# mcu.net
KiCad netlist of a schematic drawn in Altium Designer
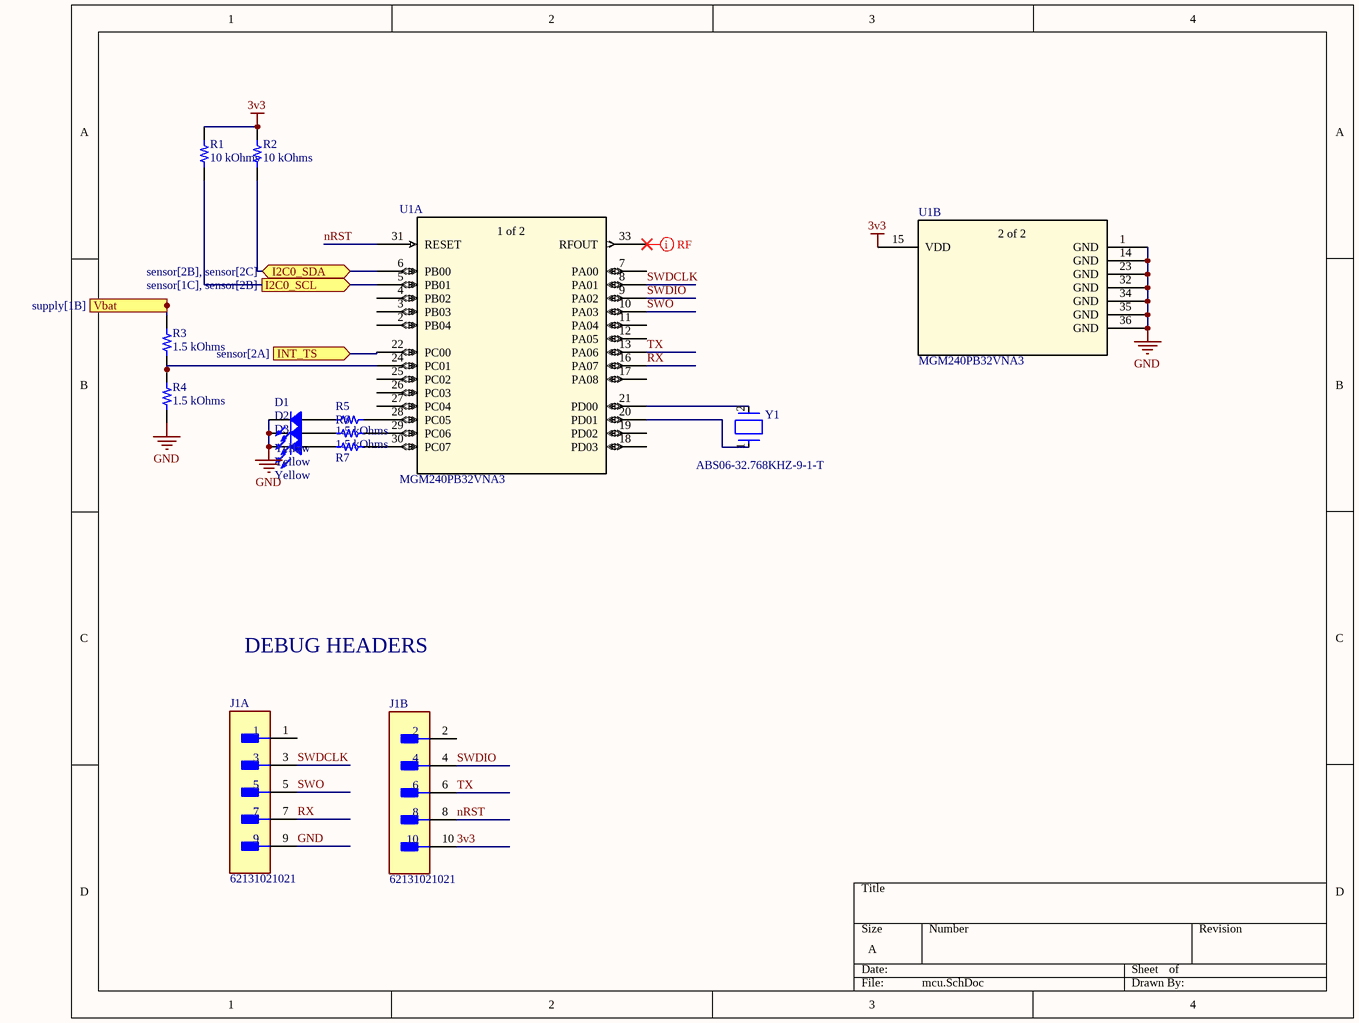
[diagram p0: mcu.SchDoc]

(export (version "E")
  (design (tool "Eeschema 10.0.6"))
  (components
    (comp (ref "D1")
      (value "Yellow")
      (footprint "LED 0402_1005 YELLOW")
      (description "0402 YELLOW")
      (fields
        (field (name "PART NUMBER") "BL-HKC37A-AV-TRB")
        (field (name "MANUFACTURER") "American Bright Optoelectronics Corporation")
      )
      (libsource (lib "Celestial Altium Library - altium_library") (part "LED"))
    )
    (comp (ref "D2")
      (value "Yellow")
      (footprint "LED 0402_1005 YELLOW")
      (description "0402 YELLOW")
      (fields
        (field (name "PART NUMBER") "BL-HKC37A-AV-TRB")
        (field (name "MANUFACTURER") "American Bright Optoelectronics Corporation")
      )
      (libsource (lib "Celestial Altium Library - altium_library") (part "LED"))
    )
    (comp (ref "D3")
      (value "Yellow")
      (footprint "LED 0402_1005 YELLOW")
      (description "0402 YELLOW")
      (fields
        (field (name "PART NUMBER") "BL-HKC37A-AV-TRB")
        (field (name "MANUFACTURER") "American Bright Optoelectronics Corporation")
      )
      (libsource (lib "Celestial Altium Library - altium_library") (part "LED"))
    )
    (comp (ref "J1")
      (value "62131021021")
      (footprint "FP-62131021021-MFG")
      (description "1.27mm SMT Straight Dual Pin Header WR-PHD")
      (libsource (lib "Altium Content Vault") (part "aca50b2a6b2128cc4a58f514acdea57"))
    )
    (comp (ref "R1")
      (value "10 kOhms")
      (footprint "RES 0402_1005")
      (description "RES 1.5K OHM 0.05% 1/10W 0402")
      (fields
        (field (name "PART NUMBER") "ERA-2VRW1501X")
        (field (name "MANUFACTURER") "Panasonic Electronic Components")
      )
      (libsource (lib "Celestial Altium Library - altium_library") (part "Resistor"))
    )
    (comp (ref "R2")
      (value "10 kOhms")
      (footprint "RES 0402_1005")
      (description "RES 1.5K OHM 0.05% 1/10W 0402")
      (fields
        (field (name "PART NUMBER") "ERA-2VRW1501X")
        (field (name "MANUFACTURER") "Panasonic Electronic Components")
      )
      (libsource (lib "Celestial Altium Library - altium_library") (part "Resistor"))
    )
    (comp (ref "R3")
      (value "1.5 kOhms")
      (footprint "RES 0402_1005")
      (description "RES 1.5K OHM 0.05% 1/10W 0402")
      (fields
        (field (name "PART NUMBER") "ERA-2VRW1501X")
        (field (name "MANUFACTURER") "Panasonic Electronic Components")
      )
      (libsource (lib "Celestial Altium Library - altium_library") (part "Resistor"))
    )
    (comp (ref "R4")
      (value "1.5 kOhms")
      (footprint "RES 0402_1005")
      (description "RES 1.5K OHM 0.05% 1/10W 0402")
      (fields
        (field (name "PART NUMBER") "ERA-2VRW1501X")
        (field (name "MANUFACTURER") "Panasonic Electronic Components")
      )
      (libsource (lib "Celestial Altium Library - altium_library") (part "Resistor"))
    )
    (comp (ref "R5")
      (value "1.5 kOhms")
      (footprint "RES 0402_1005")
      (description "RES 1.5K OHM 0.05% 1/10W 0402")
      (fields
        (field (name "PART NUMBER") "ERA-2VRW1501X")
        (field (name "MANUFACTURER") "Panasonic Electronic Components")
      )
      (libsource (lib "Celestial Altium Library - altium_library") (part "Resistor"))
    )
    (comp (ref "R6")
      (value "1.5 kOhms")
      (footprint "RES 0402_1005")
      (description "RES 1.5K OHM 0.05% 1/10W 0402")
      (fields
        (field (name "PART NUMBER") "ERA-2VRW1501X")
        (field (name "MANUFACTURER") "Panasonic Electronic Components")
      )
      (libsource (lib "Celestial Altium Library - altium_library") (part "Resistor"))
    )
    (comp (ref "R7")
      (value "~")
      (footprint "RES 0402_1005")
      (description "RES 1.5K OHM 0.05% 1/10W 0402")
      (fields
        (field (name "PART NUMBER") "ERA-2VRW1501X")
        (field (name "MANUFACTURER") "Panasonic Electronic Components")
      )
      (libsource (lib "Celestial Altium Library - altium_library") (part "Resistor"))
    )
    (comp (ref "U1")
      (value "MGM240PB32VNA3")
      (footprint "xGM240P")
      (description "No Description Available")
      (libsource (lib "MGM240PB32VNA3") (part "MGM240PB32VNA3"))
    )
    (comp (ref "Y1")
      (value "ABS06-32.768KHZ-9-1-T")
      (footprint "FP-ABS06-MFG")
      (description "Crystal 32.768kHz ±10ppm (Tol) 9pF FUND 90kΩ 2-Pin Mini-CSMD T/R")
      (fields (field (name "TOLERANCE") "10ppm"))
      (libsource (lib "Altium Content Vault") (part "c23a69dc6c9e2f18f2079038eb95dd1"))
    )
  )
  (nets
    (net (code "1") (name "/I2C0_SCL") (class "Default")
      (node (ref "R1") (pin "2") (pinfunction "2_2") (pintype "passive"))
      (node (ref "U1") (pin "5") (pinfunction "PB01_5") (pintype "bidirectional"))
    )
    (net (code "2") (name "/I2C0_SDA") (class "Default")
      (node (ref "R2") (pin "2") (pinfunction "2_2") (pintype "passive"))
      (node (ref "U1") (pin "6") (pinfunction "PB00_6") (pintype "bidirectional"))
    )
    (net (code "3") (name "/INT_TS") (class "Default")
      (node (ref "U1") (pin "22") (pinfunction "PC00_22") (pintype "bidirectional"))
    )
    (net (code "4") (name "/RX") (class "Default")
      (node (ref "J1") (pin "7") (pinfunction "7_7") (pintype "passive"))
      (node (ref "U1") (pin "16") (pinfunction "PA07_16") (pintype "bidirectional"))
    )
    (net (code "5") (name "/SWDCLK") (class "Default")
      (node (ref "J1") (pin "3") (pinfunction "3_3") (pintype "passive"))
      (node (ref "U1") (pin "8") (pinfunction "PA01_8") (pintype "bidirectional"))
    )
    (net (code "6") (name "/SWDIO") (class "Default")
      (node (ref "J1") (pin "4") (pinfunction "4_4") (pintype "passive"))
      (node (ref "U1") (pin "9") (pinfunction "PA02_9") (pintype "bidirectional"))
    )
    (net (code "7") (name "/SWO") (class "Default")
      (node (ref "J1") (pin "5") (pinfunction "5_5") (pintype "passive"))
      (node (ref "U1") (pin "10") (pinfunction "PA03_10") (pintype "bidirectional"))
    )
    (net (code "8") (name "/TX") (class "Default")
      (node (ref "J1") (pin "6") (pinfunction "6_6") (pintype "passive"))
      (node (ref "U1") (pin "13") (pinfunction "PA06_13") (pintype "bidirectional"))
    )
    (net (code "9") (name "/Vbat") (class "Default")
      (node (ref "R3") (pin "1") (pinfunction "1_1") (pintype "passive"))
    )
    (net (code "10") (name "/nRST") (class "Default")
      (node (ref "J1") (pin "8") (pinfunction "8_8") (pintype "passive"))
      (node (ref "U1") (pin "31") (pinfunction "RESET_31") (pintype "input"))
    )
    (net (code "11") (name "3v3") (class "Default")
      (node (ref "J1") (pin "10") (pinfunction "10_10") (pintype "passive"))
      (node (ref "R1") (pin "1") (pinfunction "1_1") (pintype "passive"))
      (node (ref "R2") (pin "1") (pinfunction "1_1") (pintype "passive"))
      (node (ref "U1") (pin "15") (pinfunction "VDD_15") (pintype "power_in"))
    )
    (net (code "12") (name "GND") (class "Default")
      (node (ref "D1") (pin "2") (pinfunction "2_2") (pintype "passive"))
      (node (ref "D2") (pin "2") (pinfunction "2_2") (pintype "passive"))
      (node (ref "D3") (pin "2") (pinfunction "2_2") (pintype "passive"))
      (node (ref "J1") (pin "9") (pinfunction "9_9") (pintype "passive"))
      (node (ref "R4") (pin "2") (pinfunction "2_2") (pintype "passive"))
      (node (ref "U1") (pin "1") (pinfunction "GND_1") (pintype "power_in"))
      (node (ref "U1") (pin "14") (pinfunction "GND_14") (pintype "power_in"))
      (node (ref "U1") (pin "23") (pinfunction "GND_23") (pintype "power_in"))
      (node (ref "U1") (pin "32") (pinfunction "GND_32") (pintype "power_in"))
      (node (ref "U1") (pin "34") (pinfunction "GND_34") (pintype "power_in"))
      (node (ref "U1") (pin "35") (pinfunction "GND_35") (pintype "power_in"))
      (node (ref "U1") (pin "36") (pinfunction "GND_36") (pintype "power_in"))
    )
    (net (code "13") (name "Net-(D1-Pad1)") (class "Default")
      (node (ref "D1") (pin "1") (pinfunction "1_1") (pintype "passive"))
      (node (ref "R5") (pin "1") (pinfunction "1_1") (pintype "passive"))
    )
    (net (code "14") (name "Net-(D2-Pad1)") (class "Default")
      (node (ref "D2") (pin "1") (pinfunction "1_1") (pintype "passive"))
      (node (ref "R6") (pin "1") (pinfunction "1_1") (pintype "passive"))
    )
    (net (code "15") (name "Net-(D3-Pad1)") (class "Default")
      (node (ref "D3") (pin "1") (pinfunction "1_1") (pintype "passive"))
      (node (ref "R7") (pin "1") (pinfunction "1_1") (pintype "passive"))
    )
    (net (code "16") (name "Net-(U1A-PC01)") (class "Default")
      (node (ref "R3") (pin "2") (pinfunction "2_2") (pintype "passive"))
      (node (ref "R4") (pin "1") (pinfunction "1_1") (pintype "passive"))
      (node (ref "U1") (pin "24") (pinfunction "PC01_24") (pintype "bidirectional"))
    )
    (net (code "17") (name "Net-(U1A-PC05)") (class "Default")
      (node (ref "R5") (pin "2") (pinfunction "2_2") (pintype "passive"))
      (node (ref "U1") (pin "28") (pinfunction "PC05_28") (pintype "bidirectional"))
    )
    (net (code "18") (name "Net-(U1A-PC06)") (class "Default")
      (node (ref "R6") (pin "2") (pinfunction "2_2") (pintype "passive"))
      (node (ref "U1") (pin "29") (pinfunction "PC06_29") (pintype "bidirectional"))
    )
    (net (code "19") (name "Net-(U1A-PC07)") (class "Default")
      (node (ref "R7") (pin "2") (pinfunction "2_2") (pintype "passive"))
      (node (ref "U1") (pin "30") (pinfunction "PC07_30") (pintype "bidirectional"))
    )
    (net (code "20") (name "Net-(U1A-PD00)") (class "Default")
      (node (ref "U1") (pin "21") (pinfunction "PD00_21") (pintype "bidirectional"))
      (node (ref "Y1") (pin "2") (pinfunction "2_2") (pintype "passive"))
    )
    (net (code "21") (name "Net-(U1A-PD01)") (class "Default")
      (node (ref "U1") (pin "20") (pinfunction "PD01_20") (pintype "bidirectional"))
      (node (ref "Y1") (pin "1") (pinfunction "1_1") (pintype "passive"))
    )
    (net (code "22") (name "unconnected-(J1-Pad1)") (class "Default")
      (node (ref "J1") (pin "1") (pinfunction "1_1") (pintype "passive"))
    )
    (net (code "23") (name "unconnected-(J1-Pad2)") (class "Default")
      (node (ref "J1") (pin "2") (pinfunction "2_2") (pintype "passive"))
    )
    (net (code "24") (name "unconnected-(U1A-PA00-Pad7)") (class "Default")
      (node (ref "U1") (pin "7") (pinfunction "PA00_7") (pintype "bidirectional"))
    )
    (net (code "25") (name "unconnected-(U1A-PA04-Pad11)") (class "Default")
      (node (ref "U1") (pin "11") (pinfunction "PA04_11") (pintype "bidirectional"))
    )
    (net (code "26") (name "unconnected-(U1A-PA05-Pad12)") (class "Default")
      (node (ref "U1") (pin "12") (pinfunction "PA05_12") (pintype "bidirectional"))
    )
    (net (code "27") (name "unconnected-(U1A-PA08-Pad17)") (class "Default")
      (node (ref "U1") (pin "17") (pinfunction "PA08_17") (pintype "bidirectional"))
    )
    (net (code "28") (name "unconnected-(U1A-PB02-Pad4)") (class "Default")
      (node (ref "U1") (pin "4") (pinfunction "PB02_4") (pintype "bidirectional"))
    )
    (net (code "29") (name "unconnected-(U1A-PB03-Pad3)") (class "Default")
      (node (ref "U1") (pin "3") (pinfunction "PB03_3") (pintype "bidirectional"))
    )
    (net (code "30") (name "unconnected-(U1A-PB04-Pad2)") (class "Default")
      (node (ref "U1") (pin "2") (pinfunction "PB04_2") (pintype "bidirectional"))
    )
    (net (code "31") (name "unconnected-(U1A-PC02-Pad25)") (class "Default")
      (node (ref "U1") (pin "25") (pinfunction "PC02_25") (pintype "bidirectional"))
    )
    (net (code "32") (name "unconnected-(U1A-PC03-Pad26)") (class "Default")
      (node (ref "U1") (pin "26") (pinfunction "PC03_26") (pintype "bidirectional"))
    )
    (net (code "33") (name "unconnected-(U1A-PC04-Pad27)") (class "Default")
      (node (ref "U1") (pin "27") (pinfunction "PC04_27") (pintype "bidirectional"))
    )
    (net (code "34") (name "unconnected-(U1A-PD02-Pad19)") (class "Default")
      (node (ref "U1") (pin "19") (pinfunction "PD02_19") (pintype "bidirectional"))
    )
    (net (code "35") (name "unconnected-(U1A-PD03-Pad18)") (class "Default")
      (node (ref "U1") (pin "18") (pinfunction "PD03_18") (pintype "bidirectional"))
    )
    (net (code "36") (name "unconnected-(U1A-RFOUT-Pad33)") (class "Default")
      (node (ref "U1") (pin "33") (pinfunction "RFOUT_33") (pintype "output+no_connect"))
    )
  )
)
